# WS51F640_ISP_CH552G.net
KiCad netlist of a schematic drawn in EasyEDA Pro
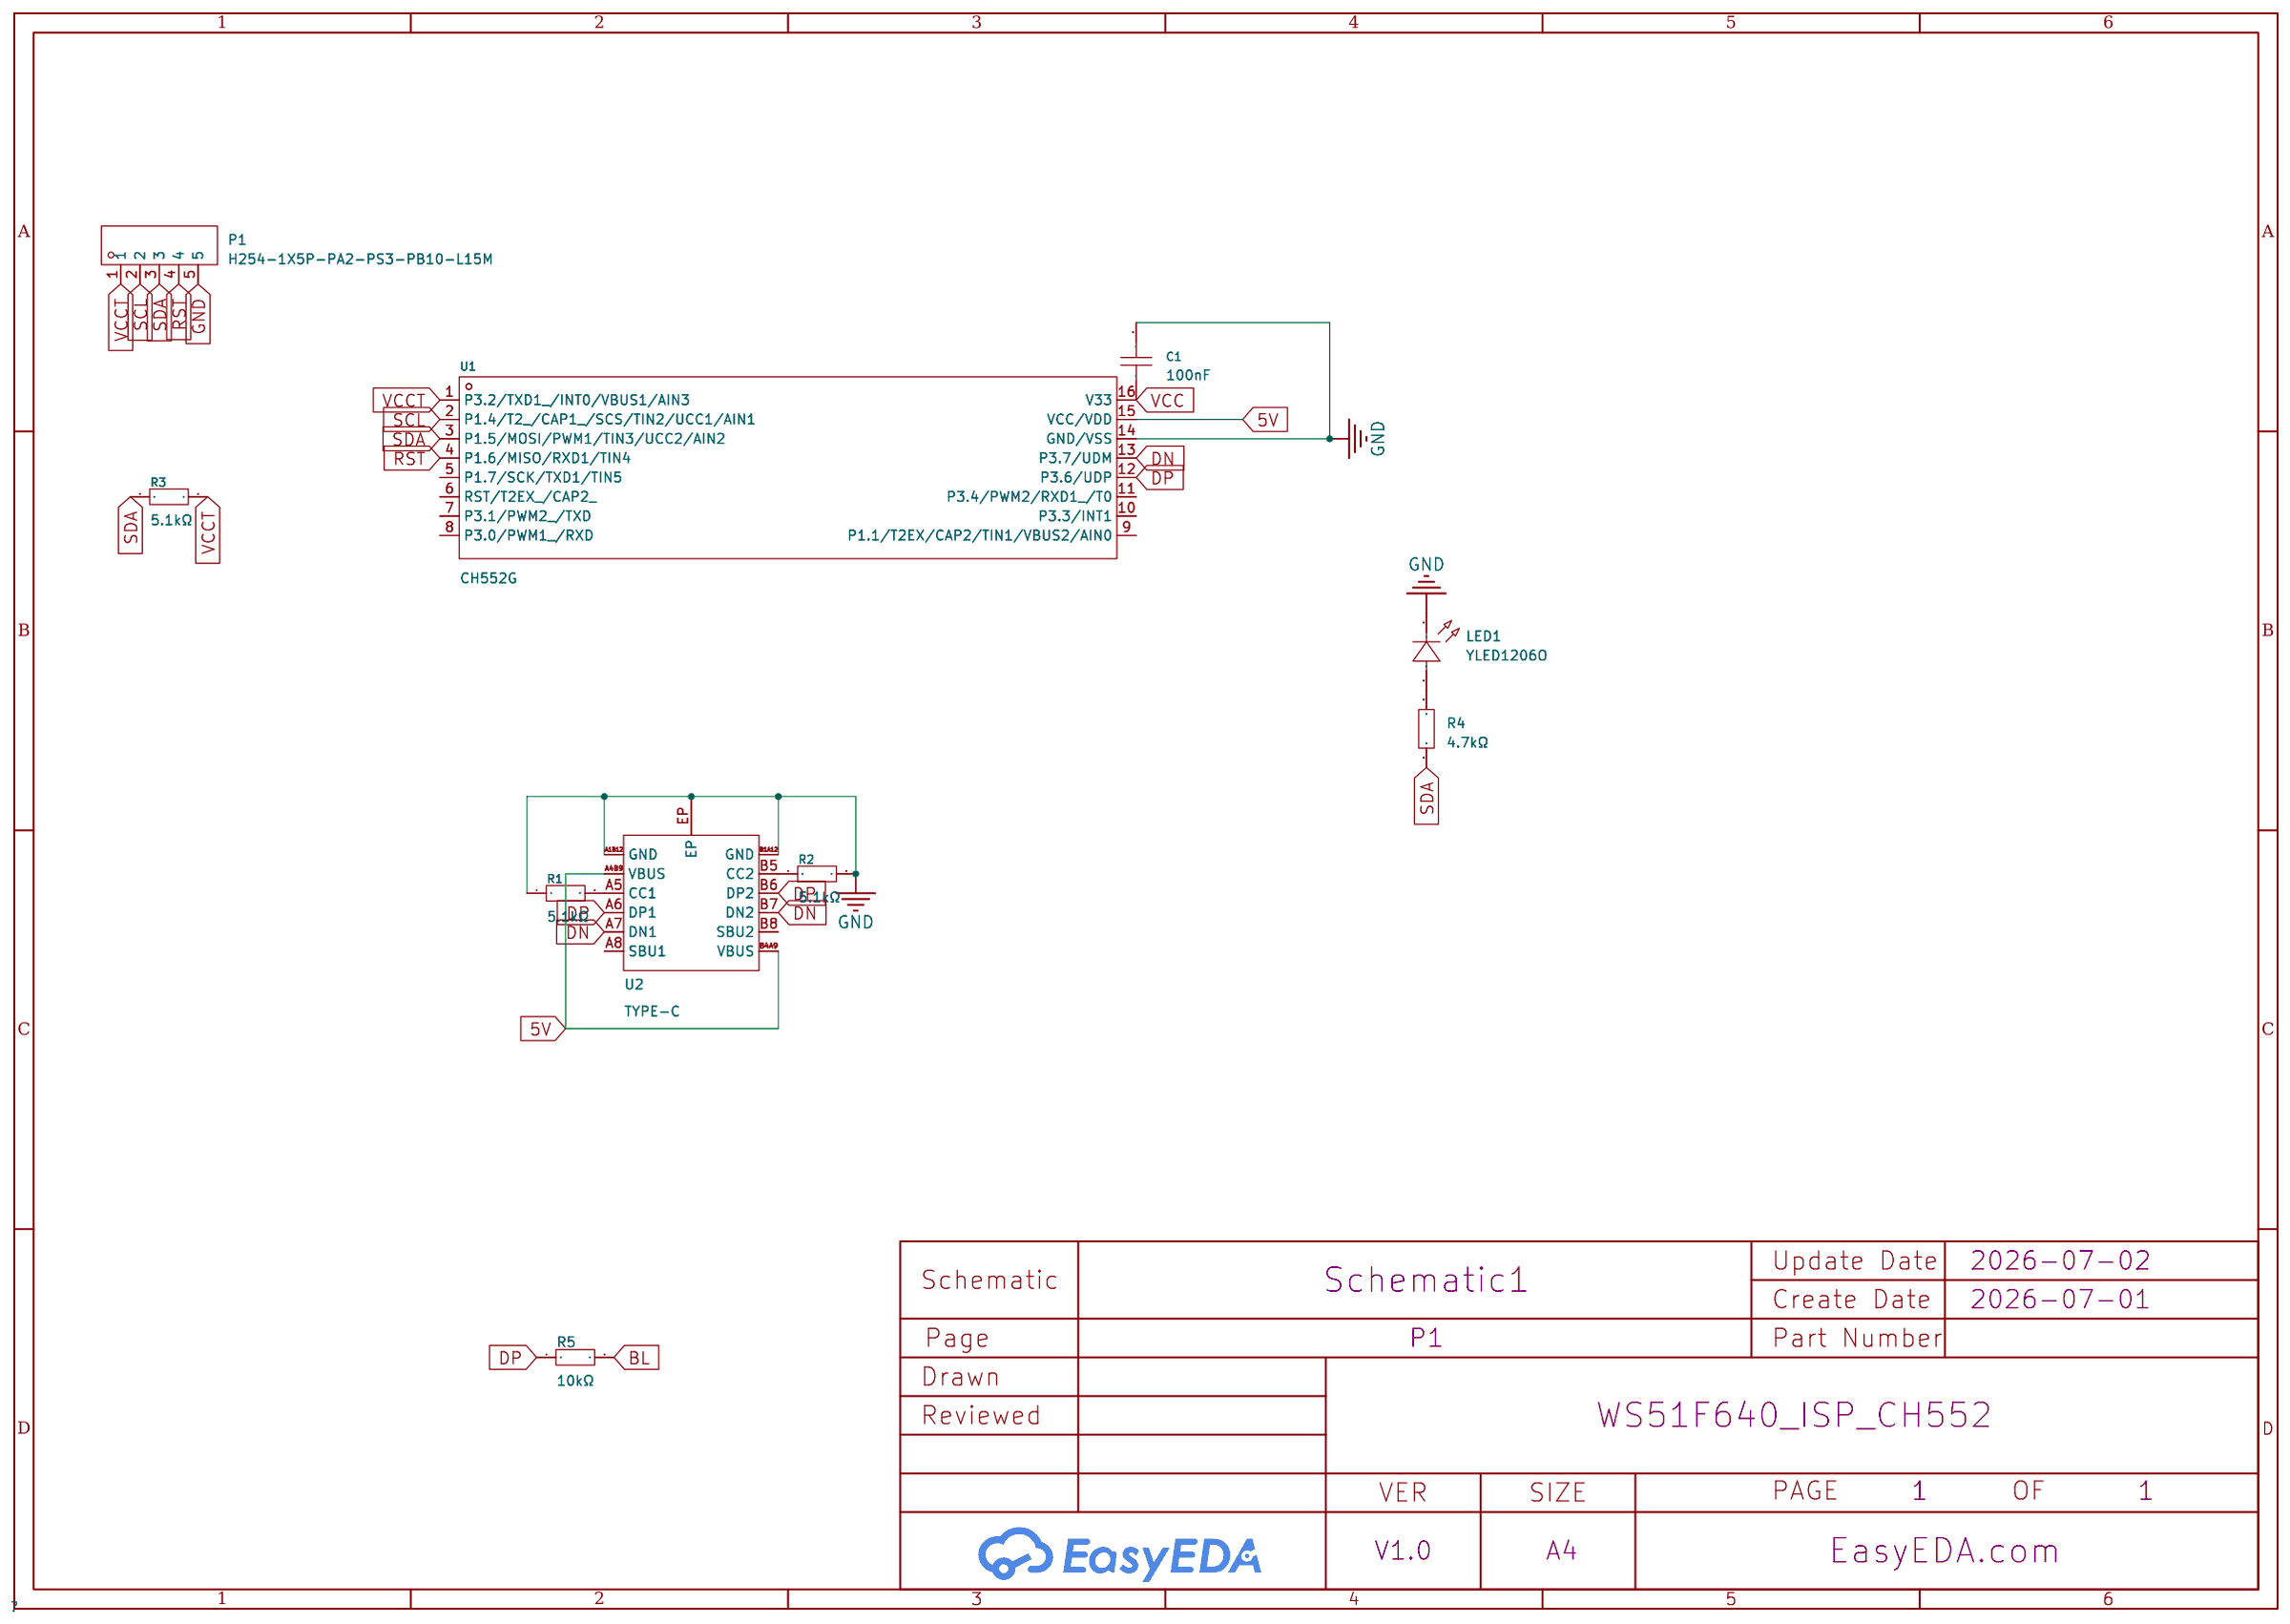
[diagram p0: schematic sheet]

(export (version "E")
  (design (tool "Eeschema 10.0.6"))
  (components
    (comp (ref "C1")
      (value "100nF")
      (footprint "easyedapro:C1206")
      (description "Capacitance:100nF Tolerance:±10% Tolerance:±10% Voltage Rating:50V Temperature Coefficient:X7R")
      (fields
        (field (name "Manufacturer Part") "C1206C104K5RAC7800")
        (field (name "Manufacturer") "KEMET(基美)")
      )
      (libsource (lib "easyedapro") (part "C1206C104K5RAC7800"))
    )
    (comp (ref "LED1")
      (value "YLED1206O")
      (footprint "easyedapro:LED1206-RD")
      (fields (field (name "Manufacturer") "YONGYUTAI(永裕泰)"))
      (libsource (lib "easyedapro") (part "YLED1206O"))
    )
    (comp (ref "P1")
      (value "H254-1X5P-PA2-PS3-PB10-L15M")
      (footprint "easyedapro:HDR-TH_5P-P2.54-V-M")
      (libsource (lib "easyedapro") (part "H254-1X5P-PA2-PS3-PB10-L15M"))
    )
    (comp (ref "R1")
      (value "5.1kΩ")
      (footprint "easyedapro:R1206")
      (fields (field (name "Manufacturer Part") "RS-06K512FT") (field (name "Manufacturer") "FH(风华)"))
      (libsource (lib "easyedapro") (part "RS-06K512FT"))
    )
    (comp (ref "R2")
      (value "5.1kΩ")
      (footprint "easyedapro:R1206")
      (fields (field (name "Manufacturer Part") "RS-06K512FT") (field (name "Manufacturer") "FH(风华)"))
      (libsource (lib "easyedapro") (part "RS-06K512FT"))
    )
    (comp (ref "R3")
      (value "5.1kΩ")
      (footprint "easyedapro:R1206")
      (fields (field (name "Manufacturer Part") "RS-06K512FT") (field (name "Manufacturer") "FH(风华)"))
      (libsource (lib "easyedapro") (part "RS-06K512FT"))
    )
    (comp (ref "R4")
      (value "4.7kΩ")
      (footprint "easyedapro:R1206")
      (fields (field (name "Manufacturer Part") "RS-06K472FT") (field (name "Manufacturer") "FH(风华)"))
      (libsource (lib "easyedapro") (part "RS-06K472FT"))
    )
    (comp (ref "R5")
      (value "10kΩ")
      (footprint "easyedapro:R1206")
      (fields (field (name "Manufacturer Part") "CR1206F41002G") (field (name "Manufacturer") "LIZ(丽智电子)"))
      (libsource (lib "easyedapro") (part "CR1206F41002G"))
    )
    (comp (ref "U1")
      (value "CH552G")
      (footprint "easyedapro:SOP-16_L10.0-W3.9-P1.27-LS6.0-BL")
      (fields (field (name "Manufacturer") "WCH(南京沁恒)"))
      (libsource (lib "easyedapro") (part "CH552G"))
    )
    (comp (ref "U2")
      (value "TYPE-C")
      (footprint "easyedapro:USB-C-SMD_TYPE-C-16P-1")
      (libsource (lib "easyedapro") (part "TYPE-C"))
    )
  )
  (nets
    (net (code "1") (name "5V") (class "Default")
      (node (ref "U1") (pin "15") (pinfunction "VCC/VDD_15") (pintype "input"))
      (node (ref "U2") (pin "A4B9") (pinfunction "VBUS_A4B9") (pintype "unspecified"))
      (node (ref "U2") (pin "B4A9") (pinfunction "VBUS_B4A9") (pintype "unspecified"))
    )
    (net (code "2") (name "BL") (class "Default")
      (node (ref "R5") (pin "2") (pinfunction "2_2") (pintype "input"))
    )
    (net (code "3") (name "DN") (class "Default")
      (node (ref "U1") (pin "13") (pinfunction "P3.7/UDM_13") (pintype "input"))
      (node (ref "U2") (pin "A7") (pinfunction "DN1_A7") (pintype "unspecified"))
      (node (ref "U2") (pin "B7") (pinfunction "DN2_B7") (pintype "unspecified"))
    )
    (net (code "4") (name "DP") (class "Default")
      (node (ref "R5") (pin "1") (pinfunction "1_1") (pintype "input"))
      (node (ref "U1") (pin "12") (pinfunction "P3.6/UDP_12") (pintype "input"))
      (node (ref "U2") (pin "A6") (pinfunction "DP1_A6") (pintype "unspecified"))
      (node (ref "U2") (pin "B6") (pinfunction "DP2_B6") (pintype "unspecified"))
    )
    (net (code "5") (name "GND") (class "Default")
      (node (ref "C1") (pin "2") (pinfunction "2_2") (pintype "input"))
      (node (ref "LED1") (pin "1") (pinfunction "K_1") (pintype "unspecified"))
      (node (ref "P1") (pin "5") (pinfunction "5_5") (pintype "unspecified"))
      (node (ref "R1") (pin "1") (pinfunction "1_1") (pintype "input"))
      (node (ref "R2") (pin "2") (pinfunction "2_2") (pintype "input"))
      (node (ref "U1") (pin "14") (pinfunction "GND/VSS_14") (pintype "input"))
      (node (ref "U2") (pin "A1B12") (pinfunction "GND_A1B12") (pintype "unspecified"))
      (node (ref "U2") (pin "B1A12") (pinfunction "GND_B1A12") (pintype "unspecified"))
      (node (ref "U2") (pin "EP") (pinfunction "EP_EP") (pintype "unspecified"))
    )
    (net (code "6") (name "Net-(LED1-A)") (class "Default")
      (node (ref "LED1") (pin "2") (pinfunction "A_2") (pintype "unspecified"))
      (node (ref "R4") (pin "2") (pinfunction "2_2") (pintype "unspecified"))
    )
    (net (code "7") (name "Net-(U2-CC1)") (class "Default")
      (node (ref "R1") (pin "2") (pinfunction "2_2") (pintype "input"))
      (node (ref "U2") (pin "A5") (pinfunction "CC1_A5") (pintype "unspecified"))
    )
    (net (code "8") (name "Net-(U2-CC2)") (class "Default")
      (node (ref "R2") (pin "1") (pinfunction "1_1") (pintype "input"))
      (node (ref "U2") (pin "B5") (pinfunction "CC2_B5") (pintype "unspecified"))
    )
    (net (code "9") (name "RST") (class "Default")
      (node (ref "P1") (pin "4") (pinfunction "4_4") (pintype "unspecified"))
      (node (ref "U1") (pin "4") (pinfunction "P1.6/MISO/RXD1/TIN4_4") (pintype "input"))
    )
    (net (code "10") (name "SCL") (class "Default")
      (node (ref "P1") (pin "2") (pinfunction "2_2") (pintype "unspecified"))
      (node (ref "U1") (pin "2") (pinfunction "P1.4/T2_/CAP1_/SCS/TIN2/UCC1/AIN1_2") (pintype "input"))
    )
    (net (code "11") (name "SDA") (class "Default")
      (node (ref "P1") (pin "3") (pinfunction "3_3") (pintype "unspecified"))
      (node (ref "R3") (pin "1") (pinfunction "1_1") (pintype "input"))
      (node (ref "R4") (pin "1") (pinfunction "1_1") (pintype "unspecified"))
      (node (ref "U1") (pin "3") (pinfunction "P1.5/MOSI/PWM1/TIN3/UCC2/AIN2_3") (pintype "input"))
    )
    (net (code "12") (name "VCC") (class "Default")
      (node (ref "C1") (pin "1") (pinfunction "1_1") (pintype "input"))
      (node (ref "U1") (pin "16") (pinfunction "V33_16") (pintype "input"))
    )
    (net (code "13") (name "VCCT") (class "Default")
      (node (ref "P1") (pin "1") (pinfunction "1_1") (pintype "unspecified"))
      (node (ref "R3") (pin "2") (pinfunction "2_2") (pintype "input"))
      (node (ref "U1") (pin "1") (pinfunction "P3.2/TXD1_/INT0/VBUS1/AIN3_1") (pintype "input"))
    )
    (net (code "14") (name "unconnected-(U1-P1.1{slash}T2EX{slash}CAP2{slash}TIN1{slash}VBUS2{slash}AIN0-Pad9)") (class "Default")
      (node (ref "U1") (pin "9") (pinfunction "P1.1/T2EX/CAP2/TIN1/VBUS2/AIN0_9") (pintype "input"))
    )
    (net (code "15") (name "unconnected-(U1-P1.7{slash}SCK{slash}TXD1{slash}TIN5-Pad5)") (class "Default")
      (node (ref "U1") (pin "5") (pinfunction "P1.7/SCK/TXD1/TIN5_5") (pintype "input"))
    )
    (net (code "16") (name "unconnected-(U1-P3.0{slash}PWM1_{slash}RXD-Pad8)") (class "Default")
      (node (ref "U1") (pin "8") (pinfunction "P3.0/PWM1_/RXD_8") (pintype "input"))
    )
    (net (code "17") (name "unconnected-(U1-P3.1{slash}PWM2_{slash}TXD-Pad7)") (class "Default")
      (node (ref "U1") (pin "7") (pinfunction "P3.1/PWM2_/TXD_7") (pintype "input"))
    )
    (net (code "18") (name "unconnected-(U1-P3.3{slash}INT1-Pad10)") (class "Default")
      (node (ref "U1") (pin "10") (pinfunction "P3.3/INT1_10") (pintype "input"))
    )
    (net (code "19") (name "unconnected-(U1-P3.4{slash}PWM2{slash}RXD1_{slash}T0-Pad11)") (class "Default")
      (node (ref "U1") (pin "11") (pinfunction "P3.4/PWM2/RXD1_/T0_11") (pintype "input"))
    )
    (net (code "20") (name "unconnected-(U1-RST{slash}T2EX_{slash}CAP2_-Pad6)") (class "Default")
      (node (ref "U1") (pin "6") (pinfunction "RST/T2EX_/CAP2__6") (pintype "input"))
    )
    (net (code "21") (name "unconnected-(U2-SBU1-PadA8)") (class "Default")
      (node (ref "U2") (pin "A8") (pinfunction "SBU1_A8") (pintype "unspecified"))
    )
    (net (code "22") (name "unconnected-(U2-SBU2-PadB8)") (class "Default")
      (node (ref "U2") (pin "B8") (pinfunction "SBU2_B8") (pintype "unspecified"))
    )
  )
)
